# electrical_base.net
KiCad netlist of a schematic drawn in EAGLE
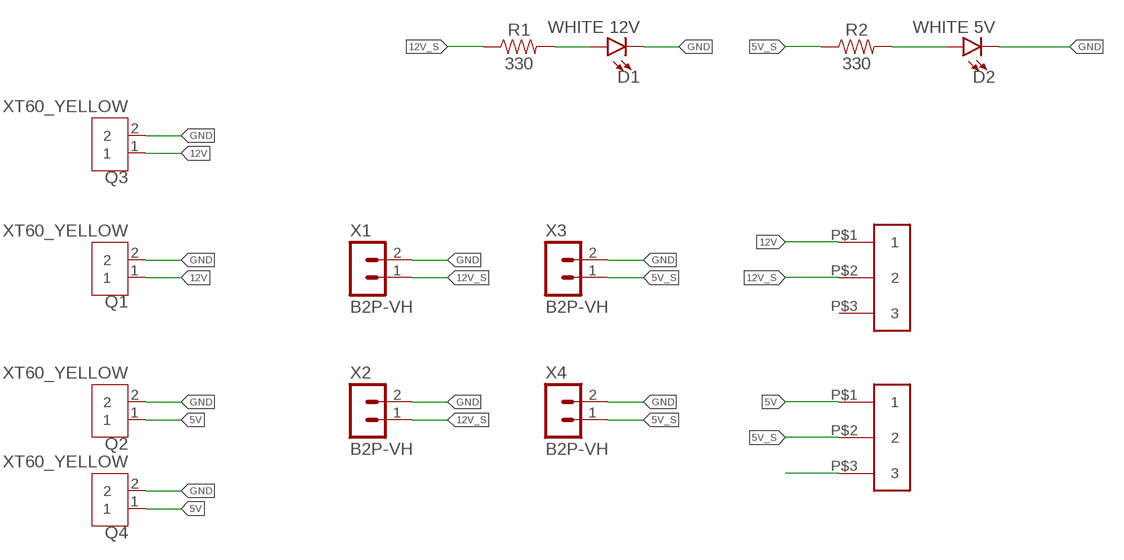
[diagram p0: schematic, sheet 1]

(export (version "E")
  (design (tool "Eeschema 10.0.6"))
  (components
    (comp (ref "D1")
      (value "WHITE 12V")
      (footprint "eagle-import:LED-1206")
      (libsource (lib "eagle-import") (part "LED-WHITE1206"))
    )
    (comp (ref "D2")
      (value "WHITE 5V")
      (footprint "eagle-import:LED-1206")
      (libsource (lib "eagle-import") (part "LED-WHITE1206"))
    )
    (comp (ref "Q1")
      (value "XT60_YELLOW")
      (footprint "eagle-import:AMASS_XT60PB-M")
      (fields (field (name "MF") "Pololu") (field (name "MP") "XT60 YELLOW"))
      (libsource (lib "eagle-import") (part "XT60_YELLOW"))
    )
    (comp (ref "Q2")
      (value "XT60_YELLOW")
      (footprint "eagle-import:AMASS_XT60PB-M")
      (fields (field (name "MF") "Pololu") (field (name "MP") "XT60 YELLOW"))
      (libsource (lib "eagle-import") (part "XT60_YELLOW"))
    )
    (comp (ref "Q3")
      (value "XT60_YELLOW")
      (footprint "eagle-import:AMASS_XT60PB-M")
      (fields (field (name "MF") "Pololu") (field (name "MP") "XT60 YELLOW"))
      (libsource (lib "eagle-import") (part "XT60_YELLOW"))
    )
    (comp (ref "Q4")
      (value "XT60_YELLOW")
      (footprint "eagle-import:AMASS_XT60PB-M")
      (fields (field (name "MF") "Pololu") (field (name "MP") "XT60 YELLOW"))
      (libsource (lib "eagle-import") (part "XT60_YELLOW"))
    )
    (comp (ref "R1")
      (value "330")
      (footprint "eagle-import:0603")
      (libsource (lib "eagle-import") (part "330OHM-0603-1/10W-1%"))
    )
    (comp (ref "R2")
      (value "330")
      (footprint "eagle-import:0603")
      (libsource (lib "eagle-import") (part "330OHM-0603-1/10W-1%"))
    )
    (comp (ref "U$1")
      (value "SWITCH_3P_4.7")
      (footprint "eagle-import:3P")
      (libsource (lib "eagle-import") (part "SWITCH_3P_4.7"))
    )
    (comp (ref "U$2")
      (value "SWITCH_3P_4.7")
      (footprint "eagle-import:3P")
      (libsource (lib "eagle-import") (part "SWITCH_3P_4.7"))
    )
    (comp (ref "X1")
      (value "B2P-VH")
      (footprint "eagle-import:B2P-VH")
      (libsource (lib "eagle-import") (part "B2P-VH"))
    )
    (comp (ref "X2")
      (value "B2P-VH")
      (footprint "eagle-import:B2P-VH")
      (libsource (lib "eagle-import") (part "B2P-VH"))
    )
    (comp (ref "X3")
      (value "B2P-VH")
      (footprint "eagle-import:B2P-VH")
      (libsource (lib "eagle-import") (part "B2P-VH"))
    )
    (comp (ref "X4")
      (value "B2P-VH")
      (footprint "eagle-import:B2P-VH")
      (libsource (lib "eagle-import") (part "B2P-VH"))
    )
  )
  (nets
    (net (code "1") (name "5V") (class "Default")
      (node (ref "Q2") (pin "1") (pinfunction "1_1") (pintype "passive"))
      (node (ref "Q4") (pin "1") (pinfunction "1_1") (pintype "passive"))
      (node (ref "U$2") (pin "P$1") (pinfunction "1_P$1") (pintype "bidirectional"))
    )
    (net (code "2") (name "5V_S") (class "Default")
      (node (ref "R2") (pin "1") (pinfunction "1_1") (pintype "passive"))
      (node (ref "U$2") (pin "P$2") (pinfunction "2_P$2") (pintype "bidirectional"))
      (node (ref "X3") (pin "1") (pinfunction "1_1") (pintype "passive"))
      (node (ref "X4") (pin "1") (pinfunction "1_1") (pintype "passive"))
    )
    (net (code "3") (name "12V") (class "Default")
      (node (ref "Q1") (pin "1") (pinfunction "1_1") (pintype "passive"))
      (node (ref "Q3") (pin "1") (pinfunction "1_1") (pintype "passive"))
      (node (ref "U$1") (pin "P$1") (pinfunction "1_P$1") (pintype "bidirectional"))
    )
    (net (code "4") (name "12V_S") (class "Default")
      (node (ref "R1") (pin "1") (pinfunction "1_1") (pintype "passive"))
      (node (ref "U$1") (pin "P$2") (pinfunction "2_P$2") (pintype "bidirectional"))
      (node (ref "X1") (pin "1") (pinfunction "1_1") (pintype "passive"))
      (node (ref "X2") (pin "1") (pinfunction "1_1") (pintype "passive"))
    )
    (net (code "5") (name "GND") (class "Default")
      (node (ref "D1") (pin "C") (pinfunction "C_C") (pintype "passive"))
      (node (ref "D2") (pin "C") (pinfunction "C_C") (pintype "passive"))
      (node (ref "Q1") (pin "2") (pinfunction "2_2") (pintype "passive"))
      (node (ref "Q2") (pin "2") (pinfunction "2_2") (pintype "passive"))
      (node (ref "Q3") (pin "2") (pinfunction "2_2") (pintype "passive"))
      (node (ref "Q4") (pin "2") (pinfunction "2_2") (pintype "passive"))
      (node (ref "X1") (pin "2") (pinfunction "2_2") (pintype "passive"))
      (node (ref "X2") (pin "2") (pinfunction "2_2") (pintype "passive"))
      (node (ref "X3") (pin "2") (pinfunction "2_2") (pintype "passive"))
      (node (ref "X4") (pin "2") (pinfunction "2_2") (pintype "passive"))
    )
    (net (code "6") (name "Net-(D1-PadA)") (class "Default")
      (node (ref "D1") (pin "A") (pinfunction "A_A") (pintype "passive"))
      (node (ref "R1") (pin "2") (pinfunction "2_2") (pintype "passive"))
    )
    (net (code "7") (name "Net-(D2-PadA)") (class "Default")
      (node (ref "D2") (pin "A") (pinfunction "A_A") (pintype "passive"))
      (node (ref "R2") (pin "2") (pinfunction "2_2") (pintype "passive"))
    )
    (net (code "8") (name "unconnected-(U$1-3-PadP$3)") (class "Default")
      (node (ref "U$1") (pin "P$3") (pinfunction "3_P$3") (pintype "bidirectional"))
    )
    (net (code "9") (name "unconnected-(U$2-3-PadP$3)") (class "Default")
      (node (ref "U$2") (pin "P$3") (pinfunction "3_P$3") (pintype "bidirectional"))
    )
  )
)
